# QFP32forZIF.net
KiCad netlist of a schematic drawn in EAGLE
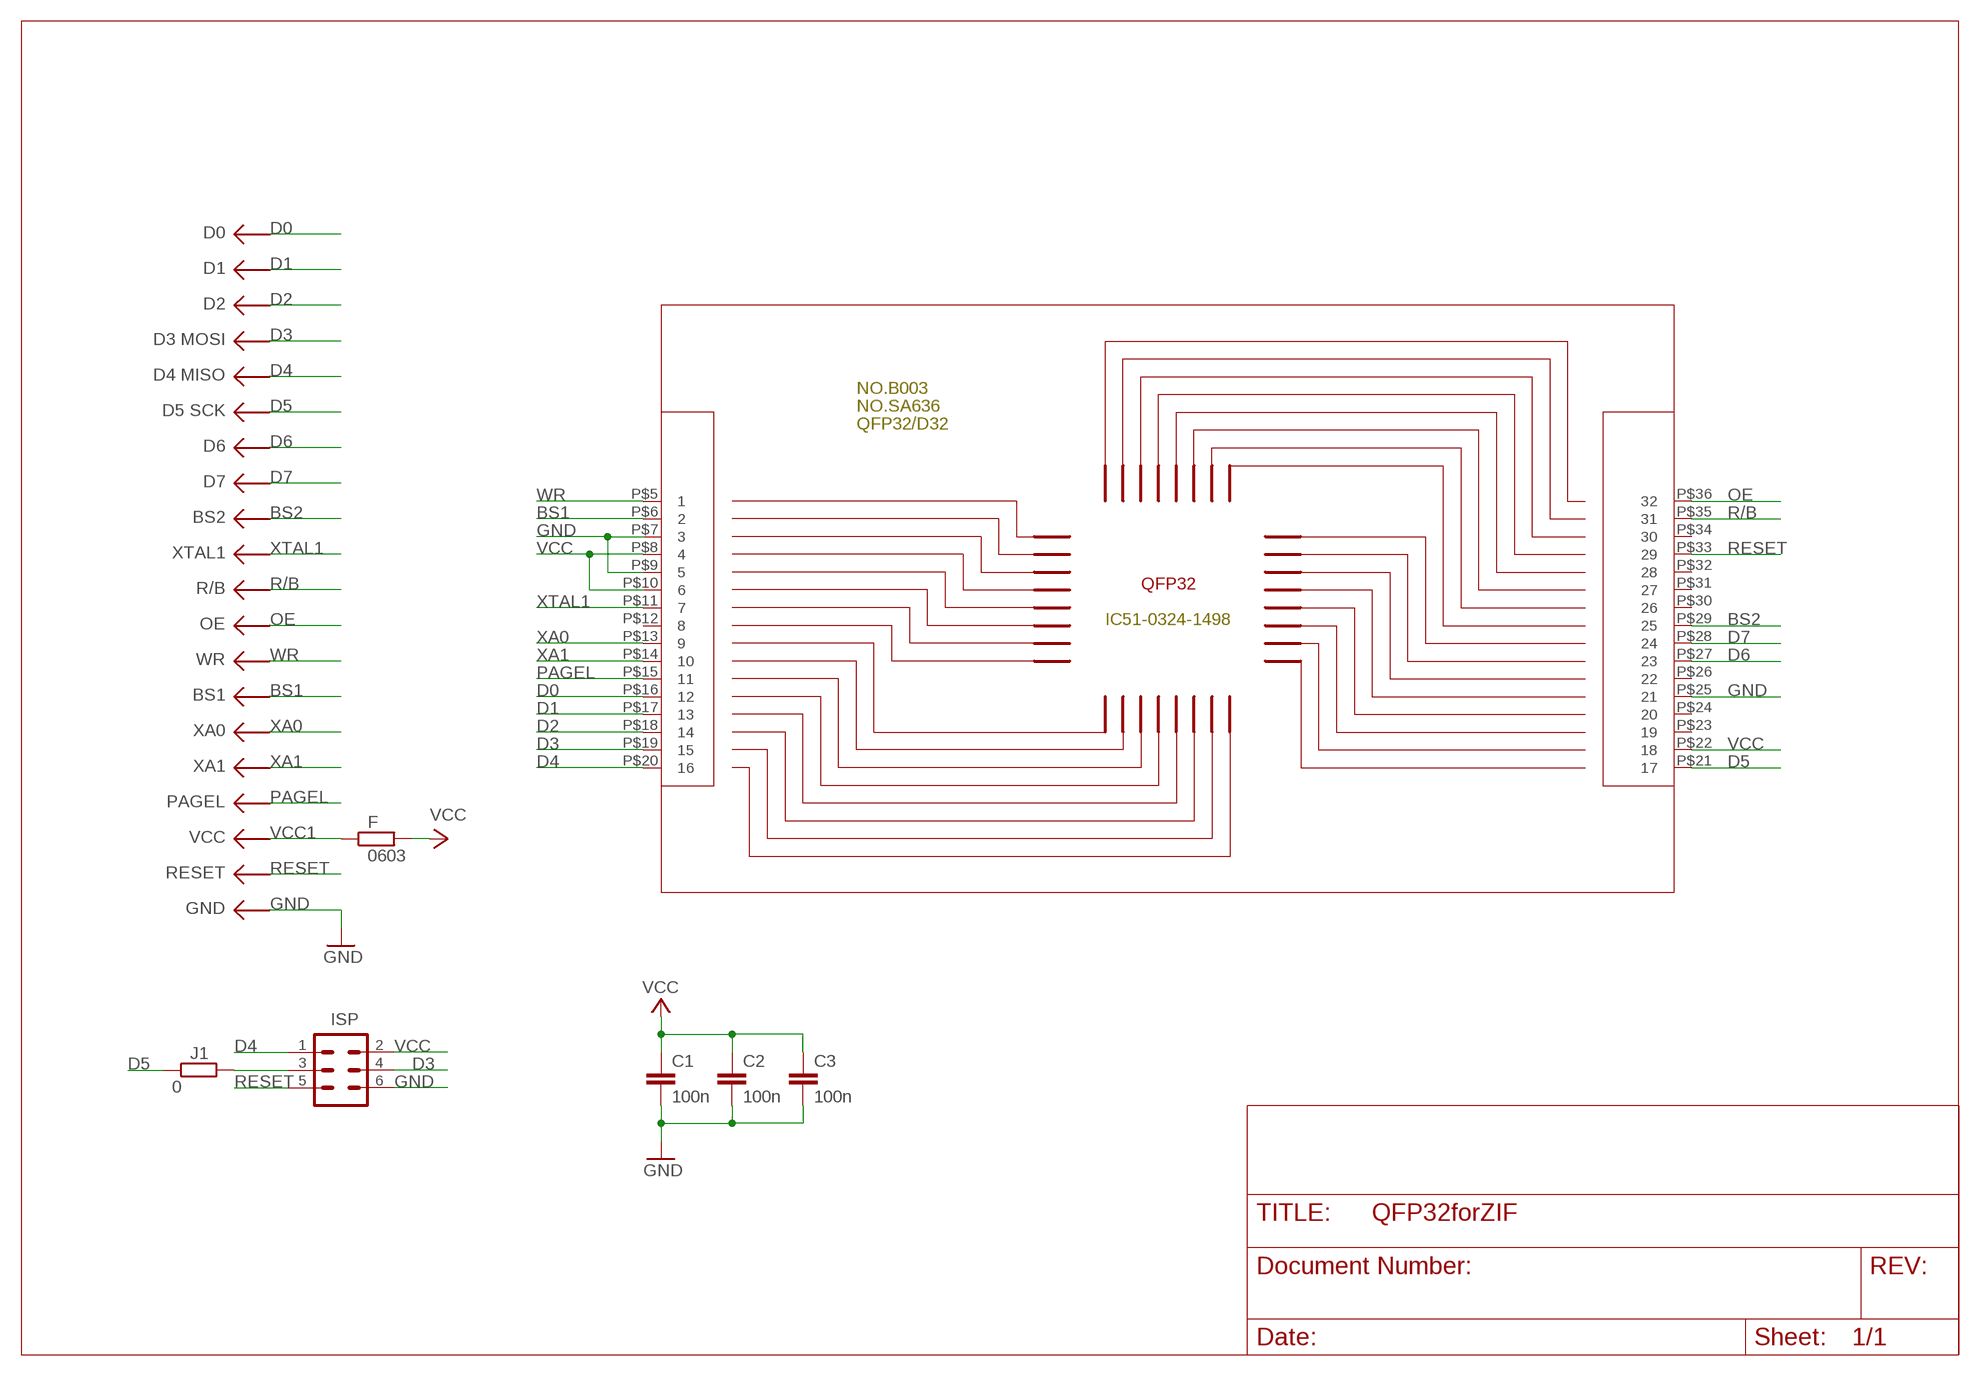
[diagram p0: schematic, sheet 1]

(export (version "E")
  (design (tool "Eeschema 10.0.6"))
  (components
    (comp (ref "C1")
      (value "100n")
      (footprint "eagle-import:RCL_C0805")
      (libsource (lib "eagle-import") (part "RCL_C-EUC0805"))
    )
    (comp (ref "C2")
      (value "100n")
      (footprint "eagle-import:RCL_C0805")
      (libsource (lib "eagle-import") (part "RCL_C-EUC0805"))
    )
    (comp (ref "C3")
      (value "100n")
      (footprint "eagle-import:RCL_C0805")
      (libsource (lib "eagle-import") (part "RCL_C-EUC0805"))
    )
    (comp (ref "F")
      (value "0603")
      (footprint "eagle-import:RCL_M0805")
      (libsource (lib "eagle-import") (part "RCL_R-EU_M0805"))
    )
    (comp (ref "ISP")
      (value "MA03-2")
      (footprint "eagle-import:MA03-2")
      (libsource (lib "eagle-import") (part "MA03-2"))
    )
    (comp (ref "J1")
      (value "0")
      (footprint "eagle-import:R1206W")
      (libsource (lib "eagle-import") (part "R-EU_R1206W"))
    )
    (comp (ref "U$1")
      (value "PROGRAMMER_P_AVR")
      (footprint "eagle-import:PROGRAMMER_P_AVR")
      (libsource (lib "eagle-import") (part "PROGRAMMER_P_AVR"))
    )
    (comp (ref "U$14")
      (value "SA636-40")
      (footprint "eagle-import:ADAPTERQFP48FORZIF")
      (libsource (lib "eagle-import") (part "SA636-40"))
    )
  )
  (nets
    (net (code "1") (name "/BS1") (class "Default")
      (node (ref "U$1") (pin "BS1") (pinfunction "BS1_BS1") (pintype "bidirectional"))
      (node (ref "U$14") (pin "P$6") (pinfunction "2_P$6") (pintype "bidirectional"))
    )
    (net (code "2") (name "/BS2") (class "Default")
      (node (ref "U$1") (pin "BS2") (pinfunction "BS2_BS2") (pintype "bidirectional"))
      (node (ref "U$14") (pin "P$29") (pinfunction "25_P$29") (pintype "bidirectional"))
    )
    (net (code "3") (name "/D0") (class "Default")
      (node (ref "U$1") (pin "D0") (pinfunction "D0_D0") (pintype "bidirectional"))
      (node (ref "U$14") (pin "P$16") (pinfunction "12_P$16") (pintype "bidirectional"))
    )
    (net (code "4") (name "/D1") (class "Default")
      (node (ref "U$1") (pin "D1") (pinfunction "D1_D1") (pintype "bidirectional"))
      (node (ref "U$14") (pin "P$17") (pinfunction "13_P$17") (pintype "bidirectional"))
    )
    (net (code "5") (name "/D2") (class "Default")
      (node (ref "U$1") (pin "D2") (pinfunction "D2_D2") (pintype "bidirectional"))
      (node (ref "U$14") (pin "P$18") (pinfunction "14_P$18") (pintype "bidirectional"))
    )
    (net (code "6") (name "/D3") (class "Default")
      (node (ref "ISP") (pin "4") (pinfunction "4_4") (pintype "passive"))
      (node (ref "U$1") (pin "D3") (pinfunction "D3_D3") (pintype "bidirectional"))
      (node (ref "U$14") (pin "P$19") (pinfunction "15_P$19") (pintype "bidirectional"))
    )
    (net (code "7") (name "/D4") (class "Default")
      (node (ref "ISP") (pin "1") (pinfunction "1_1") (pintype "passive"))
      (node (ref "U$1") (pin "D4") (pinfunction "D4_D4") (pintype "bidirectional"))
      (node (ref "U$14") (pin "P$20") (pinfunction "16_P$20") (pintype "bidirectional"))
    )
    (net (code "8") (name "/D5") (class "Default")
      (node (ref "J1") (pin "1") (pinfunction "1_1") (pintype "passive"))
      (node (ref "U$1") (pin "D5") (pinfunction "D5_D5") (pintype "bidirectional"))
      (node (ref "U$14") (pin "P$21") (pinfunction "17_P$21") (pintype "bidirectional"))
    )
    (net (code "9") (name "/D6") (class "Default")
      (node (ref "U$1") (pin "D6") (pinfunction "D6_D6") (pintype "bidirectional"))
      (node (ref "U$14") (pin "P$27") (pinfunction "23_P$27") (pintype "bidirectional"))
    )
    (net (code "10") (name "/D7") (class "Default")
      (node (ref "U$1") (pin "D7") (pinfunction "D7_D7") (pintype "bidirectional"))
      (node (ref "U$14") (pin "P$28") (pinfunction "24_P$28") (pintype "bidirectional"))
    )
    (net (code "11") (name "/OE") (class "Default")
      (node (ref "U$1") (pin "OE") (pinfunction "OE_OE") (pintype "bidirectional"))
      (node (ref "U$14") (pin "P$36") (pinfunction "32_P$36") (pintype "bidirectional"))
    )
    (net (code "12") (name "/PAGEL") (class "Default")
      (node (ref "U$1") (pin "PAGEL") (pinfunction "PAGEL_PAGEL") (pintype "bidirectional"))
      (node (ref "U$14") (pin "P$15") (pinfunction "11_P$15") (pintype "bidirectional"))
    )
    (net (code "13") (name "/RESET") (class "Default")
      (node (ref "ISP") (pin "5") (pinfunction "5_5") (pintype "passive"))
      (node (ref "U$1") (pin "RESET") (pinfunction "RESET_RESET") (pintype "bidirectional"))
      (node (ref "U$14") (pin "P$33") (pinfunction "29_P$33") (pintype "bidirectional"))
    )
    (net (code "14") (name "/R{slash}B") (class "Default")
      (node (ref "U$1") (pin "RB") (pinfunction "RB_RB") (pintype "bidirectional"))
      (node (ref "U$14") (pin "P$35") (pinfunction "31_P$35") (pintype "bidirectional"))
    )
    (net (code "15") (name "/VCC1") (class "Default")
      (node (ref "F") (pin "1") (pinfunction "1_1") (pintype "passive"))
      (node (ref "U$1") (pin "VCC") (pinfunction "VCC_VCC") (pintype "bidirectional"))
    )
    (net (code "16") (name "/WR") (class "Default")
      (node (ref "U$1") (pin "WR") (pinfunction "WR_WR") (pintype "bidirectional"))
      (node (ref "U$14") (pin "P$5") (pinfunction "1_P$5") (pintype "bidirectional"))
    )
    (net (code "17") (name "/XA0") (class "Default")
      (node (ref "U$1") (pin "XA0") (pinfunction "XA0_XA0") (pintype "bidirectional"))
      (node (ref "U$14") (pin "P$13") (pinfunction "9_P$13") (pintype "bidirectional"))
    )
    (net (code "18") (name "/XA1") (class "Default")
      (node (ref "U$1") (pin "XA1") (pinfunction "XA1_XA1") (pintype "bidirectional"))
      (node (ref "U$14") (pin "P$14") (pinfunction "10_P$14") (pintype "bidirectional"))
    )
    (net (code "19") (name "/XTAL1") (class "Default")
      (node (ref "U$1") (pin "XTAL1") (pinfunction "XTAL1_XTAL1") (pintype "bidirectional"))
      (node (ref "U$14") (pin "P$11") (pinfunction "7_P$11") (pintype "bidirectional"))
    )
    (net (code "20") (name "GND") (class "Default")
      (node (ref "C1") (pin "2") (pinfunction "2_2") (pintype "passive"))
      (node (ref "C2") (pin "2") (pinfunction "2_2") (pintype "passive"))
      (node (ref "C3") (pin "2") (pinfunction "2_2") (pintype "passive"))
      (node (ref "ISP") (pin "6") (pinfunction "6_6") (pintype "passive"))
      (node (ref "U$1") (pin "GND") (pinfunction "GND_GND") (pintype "bidirectional"))
      (node (ref "U$1") (pin "GND01") (pinfunction "GND_GND01") (pintype "bidirectional"))
      (node (ref "U$1") (pin "GND03") (pinfunction "GND_GND03") (pintype "bidirectional"))
      (node (ref "U$1") (pin "GND04") (pinfunction "GND_GND04") (pintype "bidirectional"))
      (node (ref "U$1") (pin "GND05") (pinfunction "GND_GND05") (pintype "bidirectional"))
      (node (ref "U$1") (pin "GND06") (pinfunction "GND_GND06") (pintype "bidirectional"))
      (node (ref "U$1") (pin "GND07") (pinfunction "GND_GND07") (pintype "bidirectional"))
      (node (ref "U$1") (pin "GND08") (pinfunction "GND_GND08") (pintype "bidirectional"))
      (node (ref "U$1") (pin "GND09") (pinfunction "GND_GND09") (pintype "bidirectional"))
      (node (ref "U$1") (pin "GND10") (pinfunction "GND_GND10") (pintype "bidirectional"))
      (node (ref "U$1") (pin "GND11") (pinfunction "GND_GND11") (pintype "bidirectional"))
      (node (ref "U$1") (pin "GND12") (pinfunction "GND_GND12") (pintype "bidirectional"))
      (node (ref "U$1") (pin "GND13") (pinfunction "GND_GND13") (pintype "bidirectional"))
      (node (ref "U$1") (pin "GND14") (pinfunction "GND_GND14") (pintype "bidirectional"))
      (node (ref "U$1") (pin "GND15") (pinfunction "GND_GND15") (pintype "bidirectional"))
      (node (ref "U$1") (pin "GND16") (pinfunction "GND_GND16") (pintype "bidirectional"))
      (node (ref "U$1") (pin "GND17") (pinfunction "GND_GND17") (pintype "bidirectional"))
      (node (ref "U$1") (pin "GND18") (pinfunction "GND_GND18") (pintype "bidirectional"))
      (node (ref "U$1") (pin "GND19") (pinfunction "GND_GND19") (pintype "bidirectional"))
      (node (ref "U$1") (pin "GND2") (pinfunction "GND_GND2") (pintype "bidirectional"))
      (node (ref "U$1") (pin "GND20") (pinfunction "GND_GND20") (pintype "bidirectional"))
      (node (ref "U$1") (pin "GND21") (pinfunction "GND_GND21") (pintype "bidirectional"))
      (node (ref "U$1") (pin "GND22") (pinfunction "GND_GND22") (pintype "bidirectional"))
      (node (ref "U$14") (pin "P$25") (pinfunction "21_P$25") (pintype "bidirectional"))
      (node (ref "U$14") (pin "P$7") (pinfunction "3_P$7") (pintype "bidirectional"))
      (node (ref "U$14") (pin "P$9") (pinfunction "5_P$9") (pintype "bidirectional"))
    )
    (net (code "21") (name "Net-(ISP-Pad3)") (class "Default")
      (node (ref "ISP") (pin "3") (pinfunction "3_3") (pintype "passive"))
      (node (ref "J1") (pin "2") (pinfunction "2_2") (pintype "passive"))
    )
    (net (code "22") (name "VCC") (class "Default")
      (node (ref "C1") (pin "1") (pinfunction "1_1") (pintype "passive"))
      (node (ref "C2") (pin "1") (pinfunction "1_1") (pintype "passive"))
      (node (ref "C3") (pin "1") (pinfunction "1_1") (pintype "passive"))
      (node (ref "F") (pin "2") (pinfunction "2_2") (pintype "passive"))
      (node (ref "ISP") (pin "2") (pinfunction "2_2") (pintype "passive"))
      (node (ref "U$14") (pin "P$10") (pinfunction "6_P$10") (pintype "bidirectional"))
      (node (ref "U$14") (pin "P$22") (pinfunction "18_P$22") (pintype "bidirectional"))
      (node (ref "U$14") (pin "P$8") (pinfunction "4_P$8") (pintype "bidirectional"))
    )
    (net (code "23") (name "unconnected-(U$14-8-PadP$12)") (class "Default")
      (node (ref "U$14") (pin "P$12") (pinfunction "8_P$12") (pintype "bidirectional"))
    )
    (net (code "24") (name "unconnected-(U$14-19-PadP$23)") (class "Default")
      (node (ref "U$14") (pin "P$23") (pinfunction "19_P$23") (pintype "bidirectional"))
    )
    (net (code "25") (name "unconnected-(U$14-20-PadP$24)") (class "Default")
      (node (ref "U$14") (pin "P$24") (pinfunction "20_P$24") (pintype "bidirectional"))
    )
    (net (code "26") (name "unconnected-(U$14-22-PadP$26)") (class "Default")
      (node (ref "U$14") (pin "P$26") (pinfunction "22_P$26") (pintype "bidirectional"))
    )
    (net (code "27") (name "unconnected-(U$14-26-PadP$30)") (class "Default")
      (node (ref "U$14") (pin "P$30") (pinfunction "26_P$30") (pintype "bidirectional"))
    )
    (net (code "28") (name "unconnected-(U$14-27-PadP$31)") (class "Default")
      (node (ref "U$14") (pin "P$31") (pinfunction "27_P$31") (pintype "bidirectional"))
    )
    (net (code "29") (name "unconnected-(U$14-28-PadP$32)") (class "Default")
      (node (ref "U$14") (pin "P$32") (pinfunction "28_P$32") (pintype "bidirectional"))
    )
    (net (code "30") (name "unconnected-(U$14-30-PadP$34)") (class "Default")
      (node (ref "U$14") (pin "P$34") (pinfunction "30_P$34") (pintype "bidirectional"))
    )
  )
)
